# SDC.net
KiCad netlist of a schematic drawn in Altium Designer
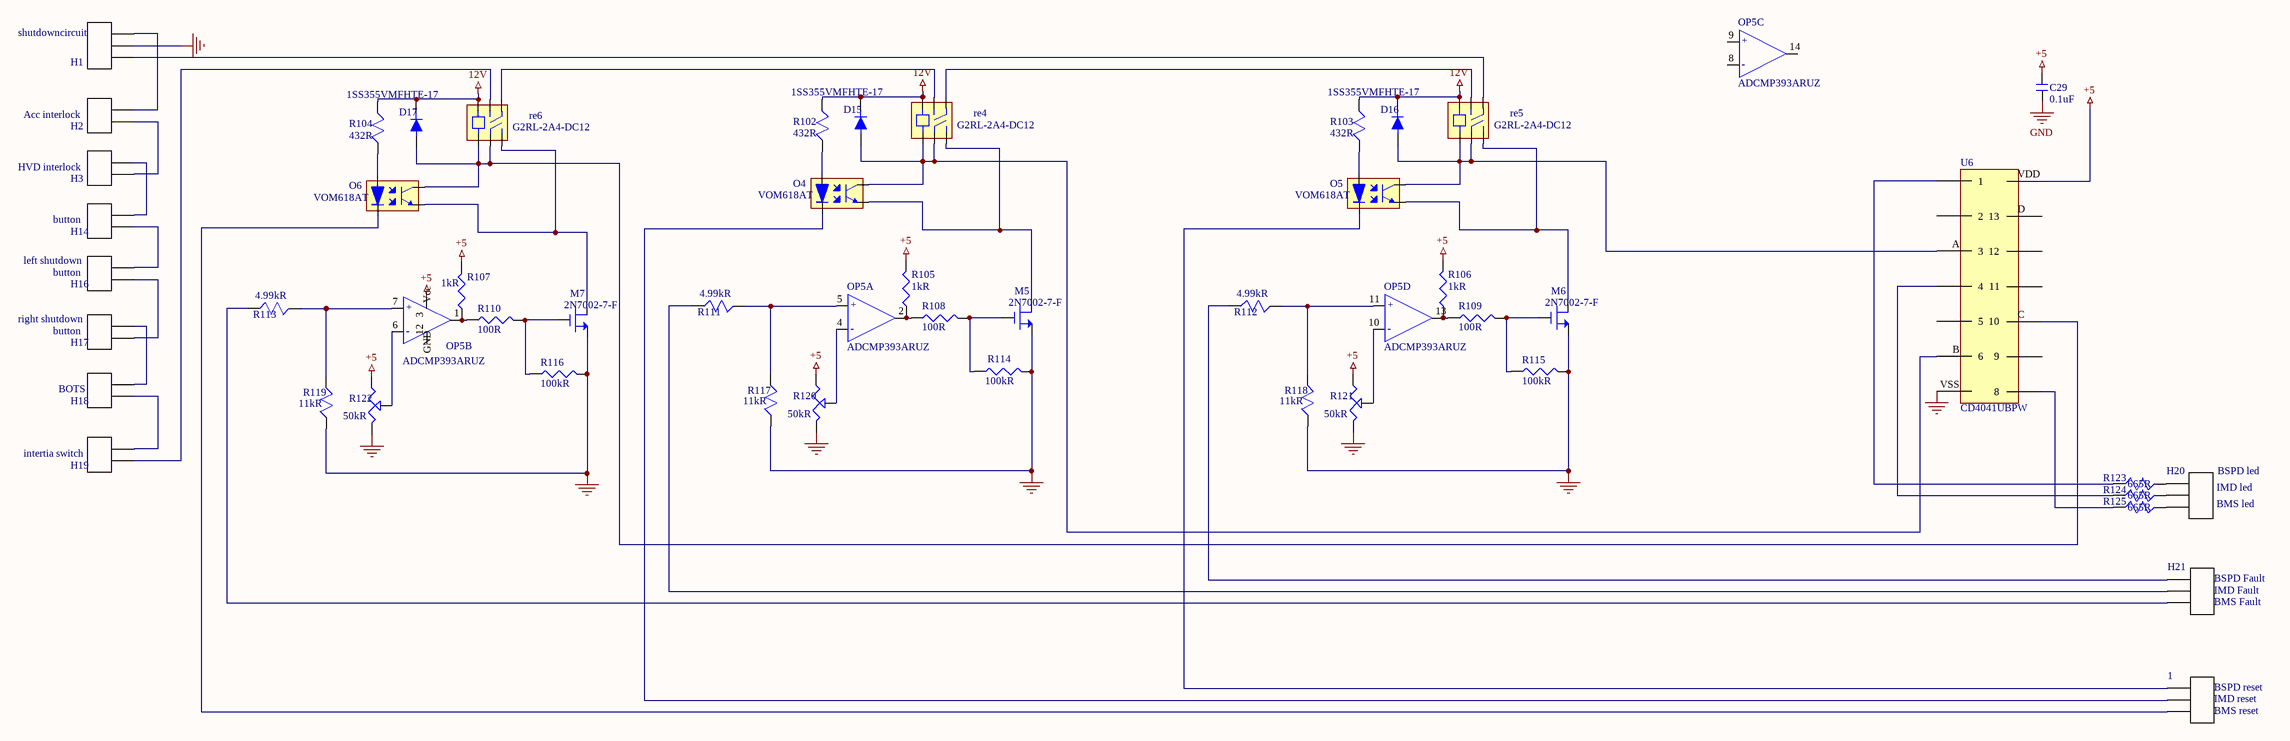
[diagram p0: SDC.SchDoc]

(export (version "E")
  (design (tool "Eeschema 10.0.6"))
  (components
    (comp (ref "1")
      (value "B3B-PH-K-S(LF)(SN)")
      (footprint "*JST_B3B-PH-K-S(LF)(SN)")
      (description "Connector Header Through Hole 3 position 0.079 _2.00mm_")
      (fields (field (name "MP") "B3B-PH-K-S_LF__SN_") (field (name "MF") "JST Sales"))
      (libsource (lib "shutdown_circuit") (part "B3B-PH-K-S(LF)(SN)_1"))
    )
    (comp (ref "C29")
      (value "0.1uF")
      (footprint "0603-0.1uF-Capacitor")
      (description "Cap Ceramic 0.1uF 50V X7R 10% Pad SMD 0603 Flexible Termination 125C Automotive")
      (fields
        (field (name "MANUFACTURER") "KEMET")
        (field (name "MANUFACTURER PART NUMBER") "C0603X104K5RAC3316")
      )
      (libsource (lib "BSPD_Schlib") (part "0.1uF-C0603X104K5RAC3316"))
    )
    (comp (ref "D15")
      (value "1SS355VMFHTE-17")
      (footprint "1SS355VMFHTE-17")
      (fields (field (name "MANUFACTURER") "Rohm"))
      (libsource (lib "shutdown_circuit") (part "1SS355VMFHTE-17"))
    )
    (comp (ref "D16")
      (value "1SS355VMFHTE-17")
      (footprint "1SS355VMFHTE-17")
      (fields (field (name "MANUFACTURER") "Rohm"))
      (libsource (lib "shutdown_circuit") (part "1SS355VMFHTE-17"))
    )
    (comp (ref "D17")
      (value "1SS355VMFHTE-17")
      (footprint "1SS355VMFHTE-17")
      (fields (field (name "MANUFACTURER") "Rohm"))
      (libsource (lib "shutdown_circuit") (part "1SS355VMFHTE-17"))
    )
    (comp (ref "H1")
      (value "B3B-PH-K-S(LF)(SN)")
      (footprint "*JST_B3B-PH-K-S(LF)(SN)")
      (description "Connector Header Through Hole 3 position 0.079 _2.00mm_")
      (fields (field (name "MP") "B3B-PH-K-S_LF__SN_") (field (name "MF") "JST Sales"))
      (libsource (lib "shutdown_circuit") (part "B3B-PH-K-S(LF)(SN)_1"))
    )
    (comp (ref "H2")
      (value "B2B-PH-K-S(LF)(SN)")
      (footprint "*JST_B2B-PH-K-S(LF)(SN)")
      (description "Connector Header Through Hole 2 position 0.079 _2.00mm_")
      (fields (field (name "MF") "JST Sales") (field (name "MP") "B2B-PH-K-S_LF__SN_"))
      (libsource (lib "shutdown_circuit") (part "B2B-PH-K-S(LF)(SN)"))
    )
    (comp (ref "H3")
      (value "B2B-PH-K-S(LF)(SN)")
      (footprint "*JST_B2B-PH-K-S(LF)(SN)")
      (description "Connector Header Through Hole 2 position 0.079 _2.00mm_")
      (fields (field (name "MF") "JST Sales") (field (name "MP") "B2B-PH-K-S_LF__SN_"))
      (libsource (lib "shutdown_circuit") (part "B2B-PH-K-S(LF)(SN)"))
    )
    (comp (ref "H14")
      (value "B2B-PH-K-S(LF)(SN)")
      (footprint "*JST_B2B-PH-K-S(LF)(SN)")
      (description "Connector Header Through Hole 2 position 0.079 _2.00mm_")
      (fields (field (name "MF") "JST Sales") (field (name "MP") "B2B-PH-K-S_LF__SN_"))
      (libsource (lib "shutdown_circuit") (part "B2B-PH-K-S(LF)(SN)"))
    )
    (comp (ref "H16")
      (value "B2B-PH-K-S(LF)(SN)")
      (footprint "*JST_B2B-PH-K-S(LF)(SN)")
      (description "Connector Header Through Hole 2 position 0.079 _2.00mm_")
      (fields (field (name "MF") "JST Sales") (field (name "MP") "B2B-PH-K-S_LF__SN_"))
      (libsource (lib "shutdown_circuit") (part "B2B-PH-K-S(LF)(SN)"))
    )
    (comp (ref "H17")
      (value "B2B-PH-K-S(LF)(SN)")
      (footprint "*JST_B2B-PH-K-S(LF)(SN)")
      (description "Connector Header Through Hole 2 position 0.079 _2.00mm_")
      (fields (field (name "MF") "JST Sales") (field (name "MP") "B2B-PH-K-S_LF__SN_"))
      (libsource (lib "shutdown_circuit") (part "B2B-PH-K-S(LF)(SN)"))
    )
    (comp (ref "H18")
      (value "B2B-PH-K-S(LF)(SN)")
      (footprint "*JST_B2B-PH-K-S(LF)(SN)")
      (description "Connector Header Through Hole 2 position 0.079 _2.00mm_")
      (fields (field (name "MF") "JST Sales") (field (name "MP") "B2B-PH-K-S_LF__SN_"))
      (libsource (lib "shutdown_circuit") (part "B2B-PH-K-S(LF)(SN)"))
    )
    (comp (ref "H19")
      (value "B2B-PH-K-S(LF)(SN)")
      (footprint "*JST_B2B-PH-K-S(LF)(SN)")
      (description "Connector Header Through Hole 2 position 0.079 _2.00mm_")
      (fields (field (name "MF") "JST Sales") (field (name "MP") "B2B-PH-K-S_LF__SN_"))
      (libsource (lib "shutdown_circuit") (part "B2B-PH-K-S(LF)(SN)"))
    )
    (comp (ref "H20")
      (value "B3B-PH-K-S(LF)(SN)")
      (footprint "*JST_B3B-PH-K-S(LF)(SN)")
      (description "Connector Header Through Hole 3 position 0.079 _2.00mm_")
      (fields (field (name "MP") "B3B-PH-K-S_LF__SN_") (field (name "MF") "JST Sales"))
      (libsource (lib "shutdown_circuit") (part "B3B-PH-K-S(LF)(SN)_1"))
    )
    (comp (ref "H21")
      (value "B3B-PH-K-S(LF)(SN)")
      (footprint "*JST_B3B-PH-K-S(LF)(SN)")
      (description "Connector Header Through Hole 3 position 0.079 _2.00mm_")
      (fields (field (name "MP") "B3B-PH-K-S_LF__SN_") (field (name "MF") "JST Sales"))
      (libsource (lib "shutdown_circuit") (part "B3B-PH-K-S(LF)(SN)_1"))
    )
    (comp (ref "M5")
      (value "2N7002-7-F")
      (footprint "2N7002-7-F")
      (fields (field (name "MANUFACTURER") "Diodes Inc.") (field (name "VOLTAGE") "60V"))
      (libsource (lib "shutdown_circuit") (part "2N7002-7-F"))
    )
    (comp (ref "M6")
      (value "2N7002-7-F")
      (footprint "2N7002-7-F")
      (fields (field (name "MANUFACTURER") "Diodes Inc.") (field (name "VOLTAGE") "60V"))
      (libsource (lib "shutdown_circuit") (part "2N7002-7-F"))
    )
    (comp (ref "M7")
      (value "2N7002-7-F")
      (footprint "2N7002-7-F")
      (fields (field (name "MANUFACTURER") "Diodes Inc.") (field (name "VOLTAGE") "60V"))
      (libsource (lib "shutdown_circuit") (part "2N7002-7-F"))
    )
    (comp (ref "O4")
      (value "VOM618AT")
      (footprint "VOM618AT")
      (description "VOM618AT DC Input Phototransistor Output Optocoupler, Surface Mount, 4-Pin SOP")
      (fields (field (name "MANUFACTURER") "Vishay"))
      (libsource (lib "shutdown_circuit") (part "VOM618AT"))
    )
    (comp (ref "O5")
      (value "VOM618AT")
      (footprint "VOM618AT")
      (description "VOM618AT DC Input Phototransistor Output Optocoupler, Surface Mount, 4-Pin SOP")
      (fields (field (name "MANUFACTURER") "Vishay"))
      (libsource (lib "shutdown_circuit") (part "VOM618AT"))
    )
    (comp (ref "O6")
      (value "VOM618AT")
      (footprint "VOM618AT")
      (description "VOM618AT DC Input Phototransistor Output Optocoupler, Surface Mount, 4-Pin SOP")
      (fields (field (name "MANUFACTURER") "Vishay"))
      (libsource (lib "shutdown_circuit") (part "VOM618AT"))
    )
    (comp (ref "OP5")
      (value "ADCMP393ARUZ")
      (description "Comparator Quad R-R I/P 5.5V 14-Pin TSSOP Tube")
      (fields (field (name "MANUFACTURER") "Analog Devices"))
      (libsource (lib "BSPD_Schlib") (part "ADCMP393ARUZ"))
    )
    (comp (ref "R102")
      (value "432R")
      (footprint "432R")
      (description "Res Thin Film 0805 432 Ohm 1% 1/8W ±50ppm/°C Molded SMD SMD Paper T/R")
      (fields
        (field (name "MANUFACTURER") "Yageo")
        (field (name "MANUFACTURER PART NUMBER") "RT0805FRE07432RL")
      )
      (libsource (lib "shutdown_circuit") (part "RT0805FRE07432RL"))
    )
    (comp (ref "R103")
      (value "432R")
      (footprint "432R")
      (description "Res Thin Film 0805 432 Ohm 1% 1/8W ±50ppm/°C Molded SMD SMD Paper T/R")
      (fields
        (field (name "MANUFACTURER") "Yageo")
        (field (name "MANUFACTURER PART NUMBER") "RT0805FRE07432RL")
      )
      (libsource (lib "shutdown_circuit") (part "RT0805FRE07432RL"))
    )
    (comp (ref "R104")
      (value "432R")
      (footprint "432R")
      (description "Res Thin Film 0805 432 Ohm 1% 1/8W ±50ppm/°C Molded SMD SMD Paper T/R")
      (fields
        (field (name "MANUFACTURER") "Yageo")
        (field (name "MANUFACTURER PART NUMBER") "RT0805FRE07432RL")
      )
      (libsource (lib "shutdown_circuit") (part "RT0805FRE07432RL"))
    )
    (comp (ref "R105")
      (value "1kR")
      (footprint "0805-Resistor")
      (description "Res Thick Film 0805 100K Ohm 1% 1/8W ±100ppm/°C Molded SMD Paper T/R")
      (fields
        (field (name "MANUFACTURER") "Vishay")
        (field (name "MANUFACTURER PART NUMBER") "CRCW0805100KFKEAC")
      )
      (libsource (lib "BSPD_Schlib_1") (part "100k-CRCW0805100KFKEAC"))
    )
    (comp (ref "R106")
      (value "1kR")
      (footprint "0805-Resistor")
      (description "Res Thick Film 0805 100K Ohm 1% 1/8W ±100ppm/°C Molded SMD Paper T/R")
      (fields
        (field (name "MANUFACTURER") "Vishay")
        (field (name "MANUFACTURER PART NUMBER") "CRCW0805100KFKEAC")
      )
      (libsource (lib "BSPD_Schlib_1") (part "100k-CRCW0805100KFKEAC"))
    )
    (comp (ref "R107")
      (value "1kR")
      (footprint "0805-Resistor")
      (description "Res Thick Film 0805 100K Ohm 1% 1/8W ±100ppm/°C Molded SMD Paper T/R")
      (fields
        (field (name "MANUFACTURER") "Vishay")
        (field (name "MANUFACTURER PART NUMBER") "CRCW0805100KFKEAC")
      )
      (libsource (lib "BSPD_Schlib_1") (part "100k-CRCW0805100KFKEAC"))
    )
    (comp (ref "R108")
      (value "100R")
      (footprint "0805-Resistor")
      (description "Res Thick Film 0805 100K Ohm 1% 1/8W ±100ppm/°C Molded SMD Paper T/R")
      (fields
        (field (name "MANUFACTURER") "Vishay")
        (field (name "MANUFACTURER PART NUMBER") "CRCW0805100KFKEAC")
      )
      (libsource (lib "BSPD_Schlib_1") (part "100k-CRCW0805100KFKEAC"))
    )
    (comp (ref "R109")
      (value "100R")
      (footprint "0805-Resistor")
      (description "Res Thick Film 0805 100K Ohm 1% 1/8W ±100ppm/°C Molded SMD Paper T/R")
      (fields
        (field (name "MANUFACTURER") "Vishay")
        (field (name "MANUFACTURER PART NUMBER") "CRCW0805100KFKEAC")
      )
      (libsource (lib "BSPD_Schlib_1") (part "100k-CRCW0805100KFKEAC"))
    )
    (comp (ref "R110")
      (value "100R")
      (footprint "0805-Resistor")
      (description "Res Thick Film 0805 100K Ohm 1% 1/8W ±100ppm/°C Molded SMD Paper T/R")
      (fields
        (field (name "MANUFACTURER") "Vishay")
        (field (name "MANUFACTURER PART NUMBER") "CRCW0805100KFKEAC")
      )
      (libsource (lib "BSPD_Schlib_1") (part "100k-CRCW0805100KFKEAC"))
    )
    (comp (ref "R111")
      (value "4.99kR")
      (footprint "4.99kR")
      (description "Res Thin Film 0805 4.99K Ohm 0.5% 1/8W ±50ppm/°C Molded SMD Paper T/R")
      (fields
        (field (name "MANUFACTURER") "Yageo")
        (field (name "MANUFACTURER PART NUMBER") "RT0805DRE074K99L")
      )
      (libsource (lib "shutdown_circuit") (part "RT0805DRE074K99L"))
    )
    (comp (ref "R112")
      (value "4.99kR")
      (footprint "4.99kR")
      (description "Res Thin Film 0805 4.99K Ohm 0.5% 1/8W ±50ppm/°C Molded SMD Paper T/R")
      (fields
        (field (name "MANUFACTURER") "Yageo")
        (field (name "MANUFACTURER PART NUMBER") "RT0805DRE074K99L")
      )
      (libsource (lib "shutdown_circuit") (part "RT0805DRE074K99L"))
    )
    (comp (ref "R113")
      (value "4.99kR")
      (footprint "4.99kR")
      (description "Res Thin Film 0805 4.99K Ohm 0.5% 1/8W ±50ppm/°C Molded SMD Paper T/R")
      (fields
        (field (name "MANUFACTURER") "Yageo")
        (field (name "MANUFACTURER PART NUMBER") "RT0805DRE074K99L")
      )
      (libsource (lib "shutdown_circuit") (part "RT0805DRE074K99L"))
    )
    (comp (ref "R114")
      (value "100kR")
      (footprint "0805-Resistor")
      (description "Res Thick Film 0805 100K Ohm 1% 1/8W ±100ppm/°C Molded SMD Paper T/R")
      (fields
        (field (name "MANUFACTURER") "Vishay")
        (field (name "MANUFACTURER PART NUMBER") "CRCW0805100KFKEAC")
      )
      (libsource (lib "BSPD_Schlib_1") (part "100k-CRCW0805100KFKEAC"))
    )
    (comp (ref "R115")
      (value "100kR")
      (footprint "0805-Resistor")
      (description "Res Thick Film 0805 100K Ohm 1% 1/8W ±100ppm/°C Molded SMD Paper T/R")
      (fields
        (field (name "MANUFACTURER") "Vishay")
        (field (name "MANUFACTURER PART NUMBER") "CRCW0805100KFKEAC")
      )
      (libsource (lib "BSPD_Schlib_1") (part "100k-CRCW0805100KFKEAC"))
    )
    (comp (ref "R116")
      (value "100kR")
      (footprint "0805-Resistor")
      (description "Res Thick Film 0805 100K Ohm 1% 1/8W ±100ppm/°C Molded SMD Paper T/R")
      (fields
        (field (name "MANUFACTURER") "Vishay")
        (field (name "MANUFACTURER PART NUMBER") "CRCW0805100KFKEAC")
      )
      (libsource (lib "BSPD_Schlib_1") (part "100k-CRCW0805100KFKEAC"))
    )
    (comp (ref "R117")
      (value "11kR")
      (footprint "Yageo 0805")
      (description "Res High Precision Thin Film 0805 11k Ohm 0.5% 1/8W ±50ppm/°C Molded Paper T/R")
      (fields
        (field (name "MANUFACTURER") "Yageo")
        (field (name "MANUFACTURER PART NUMBER") "RT0805DRE0711KL")
      )
      (libsource (lib "shutdown_circuit") (part "RT0805DRE0711KL"))
    )
    (comp (ref "R118")
      (value "11kR")
      (footprint "Yageo 0805")
      (description "Res High Precision Thin Film 0805 11k Ohm 0.5% 1/8W ±50ppm/°C Molded Paper T/R")
      (fields
        (field (name "MANUFACTURER") "Yageo")
        (field (name "MANUFACTURER PART NUMBER") "RT0805DRE0711KL")
      )
      (libsource (lib "shutdown_circuit") (part "RT0805DRE0711KL"))
    )
    (comp (ref "R119")
      (value "11kR")
      (footprint "Yageo 0805")
      (description "Res High Precision Thin Film 0805 11k Ohm 0.5% 1/8W ±50ppm/°C Molded Paper T/R")
      (fields
        (field (name "MANUFACTURER") "Yageo")
        (field (name "MANUFACTURER PART NUMBER") "RT0805DRE0711KL")
      )
      (libsource (lib "shutdown_circuit") (part "RT0805DRE0711KL"))
    )
    (comp (ref "R120")
      (value "50kR")
      (footprint "50kR-vertical")
      (description "Trimmer; Cermet; Rest 50 Kilohms; PCB; Pwr-Rtg 0.5W; Dim 0.375InLx0.19InWx0.395InH")
      (fields
        (field (name "MANUFACTURER") "Bourns")
        (field (name "MANUFACTURER PART NUMBER") "3296W-1-503LF")
      )
      (libsource (lib "BSPD_Schlib") (part "50K可變垂直-3296W-1-503LF"))
    )
    (comp (ref "R121")
      (value "50kR")
      (footprint "50kR-vertical")
      (description "Trimmer; Cermet; Rest 50 Kilohms; PCB; Pwr-Rtg 0.5W; Dim 0.375InLx0.19InWx0.395InH")
      (fields
        (field (name "MANUFACTURER") "Bourns")
        (field (name "MANUFACTURER PART NUMBER") "3296W-1-503LF")
      )
      (libsource (lib "BSPD_Schlib") (part "50K可變垂直-3296W-1-503LF"))
    )
    (comp (ref "R122")
      (value "50kR")
      (footprint "50kR-vertical")
      (description "Trimmer; Cermet; Rest 50 Kilohms; PCB; Pwr-Rtg 0.5W; Dim 0.375InLx0.19InWx0.395InH")
      (fields
        (field (name "MANUFACTURER") "Bourns")
        (field (name "MANUFACTURER PART NUMBER") "3296W-1-503LF")
      )
      (libsource (lib "BSPD_Schlib") (part "50K可變垂直-3296W-1-503LF"))
    )
    (comp (ref "R123")
      (value "665R")
      (footprint "665R,499R")
      (description "Res Thin Film 0805 665 Ohm 0.1% 1/8W ±25ppm/°C Molded SMD Paper T/R")
      (fields
        (field (name "MANUFACTURER") "TE Connectivity")
        (field (name "MANUFACTURER PART NUMBER") "RP73PF2A665RBTDF")
      )
      (libsource (lib "shutdown_circuit") (part "RP73PF2A665RBTDF"))
    )
    (comp (ref "R124")
      (value "665R")
      (footprint "665R,499R")
      (description "Res Thin Film 0805 665 Ohm 0.1% 1/8W ±25ppm/°C Molded SMD Paper T/R")
      (fields
        (field (name "MANUFACTURER") "TE Connectivity")
        (field (name "MANUFACTURER PART NUMBER") "RP73PF2A665RBTDF")
      )
      (libsource (lib "shutdown_circuit") (part "RP73PF2A665RBTDF"))
    )
    (comp (ref "R125")
      (value "665R")
      (footprint "665R,499R")
      (description "Res Thin Film 0805 665 Ohm 0.1% 1/8W ±25ppm/°C Molded SMD Paper T/R")
      (fields
        (field (name "MANUFACTURER") "TE Connectivity")
        (field (name "MANUFACTURER PART NUMBER") "RP73PF2A665RBTDF")
      )
      (libsource (lib "shutdown_circuit") (part "RP73PF2A665RBTDF"))
    )
    (comp (ref "re4")
      (value "G2RL-2A4-DC12")
      (footprint "G2RL-2A4-DC12")
      (description "Power Relay 12VDC 8A DPST-NO( (29mm 12.7mm 15.7mm)) THT")
      (fields (field (name "MANUFACTURER") "Omron"))
      (libsource (lib "shutdown_circuit") (part "G2RL-2A4-DC12"))
    )
    (comp (ref "re5")
      (value "G2RL-2A4-DC12")
      (footprint "G2RL-2A4-DC12")
      (description "Power Relay 12VDC 8A DPST-NO( (29mm 12.7mm 15.7mm)) THT")
      (fields (field (name "MANUFACTURER") "Omron"))
      (libsource (lib "shutdown_circuit") (part "G2RL-2A4-DC12"))
    )
    (comp (ref "re6")
      (value "G2RL-2A4-DC12")
      (footprint "G2RL-2A4-DC12")
      (description "Power Relay 12VDC 8A DPST-NO( (29mm 12.7mm 15.7mm)) THT")
      (fields (field (name "MANUFACTURER") "Omron"))
      (libsource (lib "shutdown_circuit") (part "G2RL-2A4-DC12"))
    )
    (comp (ref "U6")
      (value "CD4041UBPW")
      (description "Buffer 4-CH Inverting/Non-Inverting Push-Pull CMOS 14-Pin TSSOP Tube")
      (fields (field (name "MANUFACTURER") "Texas Instruments"))
      (libsource (lib "shutdown_circuit") (part "CD4041UBPW"))
    )
  )
  (nets
    (net (code "1") (name "+5") (class "Default")
      (node (ref "C29") (pin "2") (pinfunction "2_2") (pintype "passive"))
      (node (ref "OP5") (pin "3") (pinfunction "Vcc_3") (pintype "passive"))
      (node (ref "R105") (pin "2") (pinfunction "2_2") (pintype "passive"))
      (node (ref "R106") (pin "2") (pinfunction "2_2") (pintype "passive"))
      (node (ref "R107") (pin "2") (pinfunction "2_2") (pintype "passive"))
      (node (ref "R120") (pin "1") (pinfunction "1_1") (pintype "passive"))
      (node (ref "R121") (pin "1") (pinfunction "1_1") (pintype "passive"))
      (node (ref "R122") (pin "1") (pinfunction "1_1") (pintype "passive"))
      (node (ref "U6") (pin "VDD") (pinfunction "VDD_VDD") (pintype "passive"))
    )
    (net (code "2") (name "12V") (class "Default")
      (node (ref "D15") (pin "1") (pinfunction "71_1") (pintype "passive"))
      (node (ref "D16") (pin "1") (pinfunction "71_1") (pintype "passive"))
      (node (ref "D17") (pin "1") (pinfunction "71_1") (pintype "passive"))
      (node (ref "R102") (pin "2") (pinfunction "84_2") (pintype "passive"))
      (node (ref "R103") (pin "2") (pinfunction "84_2") (pintype "passive"))
      (node (ref "R104") (pin "2") (pinfunction "84_2") (pintype "passive"))
      (node (ref "re4") (pin "8") (pinfunction "121_8") (pintype "passive"))
      (node (ref "re5") (pin "8") (pinfunction "121_8") (pintype "passive"))
      (node (ref "re6") (pin "8") (pinfunction "121_8") (pintype "passive"))
    )
    (net (code "3") (name "GND") (class "Default")
      (node (ref "C29") (pin "1") (pinfunction "1_1") (pintype "passive"))
      (node (ref "H1") (pin "2") (pinfunction "2_2") (pintype "passive"))
      (node (ref "M5") (pin "2") (pinfunction "56_2") (pintype "passive"))
      (node (ref "M6") (pin "2") (pinfunction "56_2") (pintype "passive"))
      (node (ref "M7") (pin "2") (pinfunction "56_2") (pintype "passive"))
      (node (ref "R114") (pin "2") (pinfunction "2_2") (pintype "passive"))
      (node (ref "R115") (pin "2") (pinfunction "2_2") (pintype "passive"))
      (node (ref "R116") (pin "2") (pinfunction "2_2") (pintype "passive"))
      (node (ref "R117") (pin "1") (pinfunction "83_1") (pintype "passive"))
      (node (ref "R118") (pin "1") (pinfunction "83_1") (pintype "passive"))
      (node (ref "R119") (pin "1") (pinfunction "83_1") (pintype "passive"))
      (node (ref "R120") (pin "3") (pinfunction "3_3") (pintype "passive"))
      (node (ref "R121") (pin "3") (pinfunction "3_3") (pintype "passive"))
      (node (ref "R122") (pin "3") (pinfunction "3_3") (pintype "passive"))
      (node (ref "U6") (pin "VSS") (pinfunction "7_VSS") (pintype "passive"))
    )
    (net (code "4") (name "Net-(D15-70)") (class "Default")
      (node (ref "D15") (pin "2") (pinfunction "70_2") (pintype "passive"))
      (node (ref "O4") (pin "4") (pinfunction "6_4") (pintype "passive"))
      (node (ref "U6") (pin "B") (pinfunction "6_B") (pintype "passive"))
      (node (ref "re4") (pin "1") (pinfunction "122_1") (pintype "passive"))
      (node (ref "re4") (pin "3") (pinfunction "119_3") (pintype "passive"))
    )
    (net (code "5") (name "Net-(D16-70)") (class "Default")
      (node (ref "D16") (pin "2") (pinfunction "70_2") (pintype "passive"))
      (node (ref "O5") (pin "4") (pinfunction "6_4") (pintype "passive"))
      (node (ref "U6") (pin "A") (pinfunction "3_A") (pintype "passive"))
      (node (ref "re5") (pin "1") (pinfunction "122_1") (pintype "passive"))
      (node (ref "re5") (pin "3") (pinfunction "119_3") (pintype "passive"))
    )
    (net (code "6") (name "Net-(D17-70)") (class "Default")
      (node (ref "D17") (pin "2") (pinfunction "70_2") (pintype "passive"))
      (node (ref "O6") (pin "4") (pinfunction "6_4") (pintype "passive"))
      (node (ref "U6") (pin "C") (pinfunction "10_C") (pintype "passive"))
      (node (ref "re6") (pin "1") (pinfunction "122_1") (pintype "passive"))
      (node (ref "re6") (pin "3") (pinfunction "119_3") (pintype "passive"))
    )
    (net (code "7") (name "Net-(H1-Pad3)") (class "Default")
      (node (ref "H1") (pin "3") (pinfunction "3_3") (pintype "passive"))
      (node (ref "H2") (pin "2") (pinfunction "2_2") (pintype "passive"))
    )
    (net (code "8") (name "Net-(H2-Pad1)") (class "Default")
      (node (ref "H2") (pin "1") (pinfunction "1_1") (pintype "passive"))
      (node (ref "H3") (pin "1") (pinfunction "1_1") (pintype "passive"))
    )
    (net (code "9") (name "Net-(H14-Pad1)") (class "Default")
      (node (ref "H14") (pin "1") (pinfunction "1_1") (pintype "passive"))
      (node (ref "H16") (pin "2") (pinfunction "2_2") (pintype "passive"))
    )
    (net (code "10") (name "Net-(H14-Pad2)") (class "Default")
      (node (ref "H14") (pin "2") (pinfunction "2_2") (pintype "passive"))
      (node (ref "H3") (pin "2") (pinfunction "2_2") (pintype "passive"))
    )
    (net (code "11") (name "Net-(H16-Pad1)") (class "Default")
      (node (ref "H16") (pin "1") (pinfunction "1_1") (pintype "passive"))
      (node (ref "H17") (pin "1") (pinfunction "1_1") (pintype "passive"))
    )
    (net (code "12") (name "Net-(H17-Pad2)") (class "Default")
      (node (ref "H17") (pin "2") (pinfunction "2_2") (pintype "passive"))
      (node (ref "H18") (pin "2") (pinfunction "2_2") (pintype "passive"))
    )
    (net (code "13") (name "Net-(H18-Pad1)") (class "Default")
      (node (ref "H18") (pin "1") (pinfunction "1_1") (pintype "passive"))
      (node (ref "H19") (pin "2") (pinfunction "2_2") (pintype "passive"))
    )
    (net (code "14") (name "Net-(M5-54)") (class "Default")
      (node (ref "M5") (pin "1") (pinfunction "54_1") (pintype "passive"))
      (node (ref "R108") (pin "2") (pinfunction "2_2") (pintype "passive"))
      (node (ref "R114") (pin "1") (pinfunction "1_1") (pintype "passive"))
    )
    (net (code "15") (name "Net-(M5-55)") (class "Default")
      (node (ref "M5") (pin "3") (pinfunction "55_3") (pintype "passive"))
      (node (ref "O4") (pin "3") (pinfunction "9_3") (pintype "passive"))
      (node (ref "re4") (pin "4") (pinfunction "120_4") (pintype "passive"))
    )
    (net (code "16") (name "Net-(M6-54)") (class "Default")
      (node (ref "M6") (pin "1") (pinfunction "54_1") (pintype "passive"))
      (node (ref "R109") (pin "2") (pinfunction "2_2") (pintype "passive"))
      (node (ref "R115") (pin "1") (pinfunction "1_1") (pintype "passive"))
    )
    (net (code "17") (name "Net-(M6-55)") (class "Default")
      (node (ref "M6") (pin "3") (pinfunction "55_3") (pintype "passive"))
      (node (ref "O5") (pin "3") (pinfunction "9_3") (pintype "passive"))
      (node (ref "re5") (pin "4") (pinfunction "120_4") (pintype "passive"))
    )
    (net (code "18") (name "Net-(M7-54)") (class "Default")
      (node (ref "M7") (pin "1") (pinfunction "54_1") (pintype "passive"))
      (node (ref "R110") (pin "2") (pinfunction "2_2") (pintype "passive"))
      (node (ref "R116") (pin "1") (pinfunction "1_1") (pintype "passive"))
    )
    (net (code "19") (name "Net-(M7-55)") (class "Default")
      (node (ref "M7") (pin "3") (pinfunction "55_3") (pintype "passive"))
      (node (ref "O6") (pin "3") (pinfunction "9_3") (pintype "passive"))
      (node (ref "re6") (pin "4") (pinfunction "120_4") (pintype "passive"))
    )
    (net (code "20") (name "Net-(O4-5)") (class "Default")
      (node (ref "1") (pin "2") (pinfunction "2_2") (pintype "passive"))
      (node (ref "O4") (pin "2") (pinfunction "5_2") (pintype "passive"))
    )
    (net (code "21") (name "Net-(O4-7)") (class "Default")
      (node (ref "O4") (pin "1") (pinfunction "7_1") (pintype "passive"))
      (node (ref "R102") (pin "1") (pinfunction "83_1") (pintype "passive"))
    )
    (net (code "22") (name "Net-(O5-5)") (class "Default")
      (node (ref "1") (pin "1") (pinfunction "1_1") (pintype "passive"))
      (node (ref "O5") (pin "2") (pinfunction "5_2") (pintype "passive"))
    )
    (net (code "23") (name "Net-(O5-7)") (class "Default")
      (node (ref "O5") (pin "1") (pinfunction "7_1") (pintype "passive"))
      (node (ref "R103") (pin "1") (pinfunction "83_1") (pintype "passive"))
    )
    (net (code "24") (name "Net-(O6-5)") (class "Default")
      (node (ref "1") (pin "3") (pinfunction "3_3") (pintype "passive"))
      (node (ref "O6") (pin "2") (pinfunction "5_2") (pintype "passive"))
    )
    (net (code "25") (name "Net-(O6-7)") (class "Default")
      (node (ref "O6") (pin "1") (pinfunction "7_1") (pintype "passive"))
      (node (ref "R104") (pin "1") (pinfunction "83_1") (pintype "passive"))
    )
    (net (code "26") (name "Net-(OP5A-+)") (class "Default")
      (node (ref "OP5") (pin "5") (pinfunction "+_5") (pintype "passive"))
      (node (ref "R111") (pin "2") (pinfunction "84_2") (pintype "passive"))
      (node (ref "R117") (pin "2") (pinfunction "84_2") (pintype "passive"))
    )
    (net (code "27") (name "Net-(OP5A--)") (class "Default")
      (node (ref "OP5") (pin "4") (pinfunction "-_4") (pintype "passive"))
      (node (ref "R120") (pin "2") (pinfunction "2_2") (pintype "passive"))
    )
    (net (code "28") (name "Net-(OP5A-out)") (class "Default")
      (node (ref "OP5") (pin "2") (pinfunction "out_2") (pintype "passive"))
      (node (ref "R105") (pin "1") (pinfunction "1_1") (pintype "passive"))
      (node (ref "R108") (pin "1") (pinfunction "1_1") (pintype "passive"))
    )
    (net (code "29") (name "Net-(OP5B-+)") (class "Default")
      (node (ref "OP5") (pin "7") (pinfunction "+_7") (pintype "passive"))
      (node (ref "R113") (pin "2") (pinfunction "84_2") (pintype "passive"))
      (node (ref "R119") (pin "2") (pinfunction "84_2") (pintype "passive"))
    )
    (net (code "30") (name "Net-(OP5B--)") (class "Default")
      (node (ref "OP5") (pin "6") (pinfunction "-_6") (pintype "passive"))
      (node (ref "R122") (pin "2") (pinfunction "2_2") (pintype "passive"))
    )
    (net (code "31") (name "Net-(OP5B-out)") (class "Default")
      (node (ref "OP5") (pin "1") (pinfunction "out_1") (pintype "passive"))
      (node (ref "R107") (pin "1") (pinfunction "1_1") (pintype "passive"))
      (node (ref "R110") (pin "1") (pinfunction "1_1") (pintype "passive"))
    )
    (net (code "32") (name "Net-(OP5D-+)") (class "Default")
      (node (ref "OP5") (pin "11") (pinfunction "+_11") (pintype "passive"))
      (node (ref "R112") (pin "2") (pinfunction "84_2") (pintype "passive"))
      (node (ref "R118") (pin "2") (pinfunction "84_2") (pintype "passive"))
    )
    (net (code "33") (name "Net-(OP5D--)") (class "Default")
      (node (ref "OP5") (pin "10") (pinfunction "-_10") (pintype "passive"))
      (node (ref "R121") (pin "2") (pinfunction "2_2") (pintype "passive"))
    )
    (net (code "34") (name "Net-(OP5D-out)") (class "Default")
      (node (ref "OP5") (pin "13") (pinfunction "out_13") (pintype "passive"))
      (node (ref "R106") (pin "1") (pinfunction "1_1") (pintype "passive"))
      (node (ref "R109") (pin "1") (pinfunction "1_1") (pintype "passive"))
    )
    (net (code "35") (name "Net-(R111-83)") (class "Default")
      (node (ref "H21") (pin "2") (pinfunction "2_2") (pintype "passive"))
      (node (ref "R111") (pin "1") (pinfunction "83_1") (pintype "passive"))
    )
    (net (code "36") (name "Net-(R112-83)") (class "Default")
      (node (ref "H21") (pin "1") (pinfunction "1_1") (pintype "passive"))
      (node (ref "R112") (pin "1") (pinfunction "83_1") (pintype "passive"))
    )
    (net (code "37") (name "Net-(R113-83)") (class "Default")
      (node (ref "H21") (pin "3") (pinfunction "3_3") (pintype "passive"))
      (node (ref "R113") (pin "1") (pinfunction "83_1") (pintype "passive"))
    )
    (net (code "38") (name "Net-(R123-83)") (class "Default")
      (node (ref "H20") (pin "1") (pinfunction "1_1") (pintype "passive"))
      (node (ref "R123") (pin "1") (pinfunction "83_1") (pintype "passive"))
    )
    (net (code "39") (name "Net-(R123-84)") (class "Default")
      (node (ref "R123") (pin "2") (pinfunction "84_2") (pintype "passive"))
      (node (ref "U6") (pin "1") (pinfunction "1_1") (pintype "passive"))
    )
    (net (code "40") (name "Net-(R124-83)") (class "Default")
      (node (ref "H20") (pin "2") (pinfunction "2_2") (pintype "passive"))
      (node (ref "R124") (pin "1") (pinfunction "83_1") (pintype "passive"))
    )
    (net (code "41") (name "Net-(R124-84)") (class "Default")
      (node (ref "R124") (pin "2") (pinfunction "84_2") (pintype "passive"))
      (node (ref "U6") (pin "4") (pinfunction "4_4") (pintype "passive"))
    )
    (net (code "42") (name "Net-(R125-83)") (class "Default")
      (node (ref "H20") (pin "3") (pinfunction "3_3") (pintype "passive"))
      (node (ref "R125") (pin "1") (pinfunction "83_1") (pintype "passive"))
    )
    (net (code "43") (name "Net-(R125-84)") (class "Default")
      (node (ref "R125") (pin "2") (pinfunction "84_2") (pintype "passive"))
      (node (ref "U6") (pin "8") (pinfunction "8_8") (pintype "passive"))
    )
    (net (code "44") (name "Net-(re4-117)") (class "Default")
      (node (ref "re4") (pin "6") (pinfunction "117_6") (pintype "passive"))
      (node (ref "re6") (pin "5") (pinfunction "118_5") (pintype "passive"))
    )
    (net (code "45") (name "Net-(re4-118)") (class "Default")
      (node (ref "re4") (pin "5") (pinfunction "118_5") (pintype "passive"))
      (node (ref "re5") (pin "6") (pinfunction "117_6") (pintype "passive"))
    )
    (net (code "46") (name "Net-(re5-118)") (class "Default")
      (node (ref "H1") (pin "1") (pinfunction "1_1") (pintype "passive"))
      (node (ref "re5") (pin "5") (pinfunction "118_5") (pintype "passive"))
    )
    (net (code "47") (name "Net-(re6-117)") (class "Default")
      (node (ref "H19") (pin "1") (pinfunction "1_1") (pintype "passive"))
      (node (ref "re6") (pin "6") (pinfunction "117_6") (pintype "passive"))
    )
    (net (code "48") (name "unconnected-(OP5B-GND-Pad12)") (class "Default")
      (node (ref "OP5") (pin "12") (pinfunction "GND_12") (pintype "passive"))
    )
    (net (code "49") (name "unconnected-(OP5C-+-Pad9)") (class "Default")
      (node (ref "OP5") (pin "9") (pinfunction "+_9") (pintype "passive"))
    )
    (net (code "50") (name "unconnected-(OP5C---Pad8)") (class "Default")
      (node (ref "OP5") (pin "8") (pinfunction "-_8") (pintype "passive"))
    )
    (net (code "51") (name "unconnected-(OP5C-out-Pad14)") (class "Default")
      (node (ref "OP5") (pin "14") (pinfunction "out_14") (pintype "passive"))
    )
    (net (code "52") (name "unconnected-(U6-13-PadD)") (class "Default")
      (node (ref "U6") (pin "D") (pinfunction "13_D") (pintype "passive"))
    )
    (net (code "53") (name "unconnected-(U6-Pad2)") (class "Default")
      (node (ref "U6") (pin "2") (pinfunction "2_2") (pintype "passive"))
    )
    (net (code "54") (name "unconnected-(U6-Pad5)") (class "Default")
      (node (ref "U6") (pin "5") (pinfunction "5_5") (pintype "passive"))
    )
    (net (code "55") (name "unconnected-(U6-Pad9)") (class "Default")
      (node (ref "U6") (pin "9") (pinfunction "9_9") (pintype "passive"))
    )
    (net (code "56") (name "unconnected-(U6-Pad11)") (class "Default")
      (node (ref "U6") (pin "11") (pinfunction "11_11") (pintype "passive"))
    )
    (net (code "57") (name "unconnected-(U6-Pad12)") (class "Default")
      (node (ref "U6") (pin "12") (pinfunction "12_12") (pintype "passive"))
    )
  )
)
